# RS232_485.net
KiCad netlist of a schematic drawn in Altium Designer
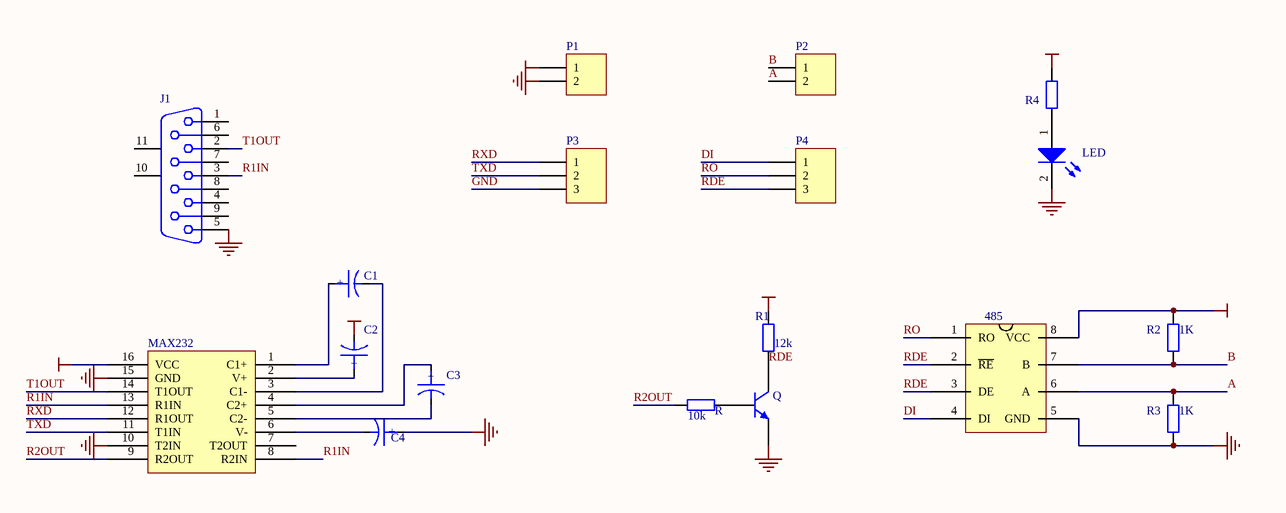
[diagram p0: RS232转485通讯模块.SCHDOC]

(export (version "E")
  (design (tool "Eeschema 10.0.6"))
  (components
    (comp (ref "485") (value "~") (footprint "DIP-8") (libsource (lib "zxcourhc") (part "485芯片")))
    (comp (ref "C1")
      (value "~")
      (footprint "C-DJ-4")
      (description "Capacitor")
      (libsource (lib "") (part "CAPACITOR POL_1"))
    )
    (comp (ref "C2")
      (value "~")
      (footprint "C-DJ-4")
      (description "Capacitor")
      (libsource (lib "") (part "CAPACITOR POL_1"))
    )
    (comp (ref "C3")
      (value "~")
      (footprint "C-DJ-4")
      (description "Capacitor")
      (libsource (lib "") (part "CAPACITOR POL_1"))
    )
    (comp (ref "C4")
      (value "~")
      (footprint "C-DJ-4")
      (description "Capacitor")
      (libsource (lib "*") (part "CAPACITOR POL"))
    )
    (comp (ref "J1")
      (value "~")
      (footprint "DSUB1.385-2H9")
      (description "Receptacle Assembly, 9 Position, Right Angle")
      (fields (field (name "PUBLISHER") "Altium Limited"))
      (libsource (lib "Miscellaneous Connectors") (part "D Connector 9"))
    )
    (comp (ref "LED")
      (value "~")
      (footprint "TP-0805-D")
      (description "发光二极管")
      (fields (field (name "PUBLISHER") "Altium Limited"))
      (libsource (lib "zxcourhc") (part "LED"))
    )
    (comp (ref "MAX232") (value "~") (footprint "DIP16") (libsource (lib "*") (part "MAX232")))
    (comp (ref "P1")
      (value "~")
      (footprint "JK128_2")
      (description "排针——2")
      (fields (field (name "PUBLISHER") "Altium Limited"))
      (libsource (lib "zxcourhc") (part "PZ_2"))
    )
    (comp (ref "P2")
      (value "~")
      (footprint "JK128_2")
      (description "排针——2")
      (fields (field (name "PUBLISHER") "Altium Limited"))
      (libsource (lib "zxcourhc") (part "PZ_2"))
    )
    (comp (ref "P3")
      (value "~")
      (footprint "HDR-3")
      (description "排针——3")
      (fields (field (name "PUBLISHER") "Altium Limited"))
      (libsource (lib "zxcourhc") (part "PZ_3"))
    )
    (comp (ref "P4")
      (value "~")
      (footprint "HDR-3")
      (description "排针——3")
      (fields (field (name "PUBLISHER") "Altium Limited"))
      (libsource (lib "zxcourhc") (part "PZ_3"))
    )
    (comp (ref "Q")
      (value "~")
      (footprint "SO-G3")
      (description "贴片三极管——NPN")
      (fields (field (name "PUBLISHER") "Altium Limited"))
      (libsource (lib "zxcourhc") (part "TPSJG_NPN"))
    )
    (comp (ref "R")
      (value "10k")
      (footprint "TP-0805-R")
      (description "电阻")
      (fields (field (name "PUBLISHER") "Altium Limited"))
      (libsource (lib "") (part "Res_2"))
    )
    (comp (ref "R1")
      (value "12k")
      (footprint "TP-0805-R")
      (description "电阻")
      (fields (field (name "PUBLISHER") "Altium Limited"))
      (libsource (lib "") (part "Res_1"))
    )
    (comp (ref "R2")
      (value "1K")
      (footprint "TP-0805-R")
      (description "电阻")
      (fields (field (name "PUBLISHER") "Altium Limited"))
      (libsource (lib "zxcourhc") (part "Res"))
    )
    (comp (ref "R3")
      (value "1K")
      (footprint "TP-0805-R")
      (description "电阻")
      (fields (field (name "PUBLISHER") "Altium Limited"))
      (libsource (lib "zxcourhc") (part "Res"))
    )
    (comp (ref "R4")
      (value "~")
      (footprint "TP-0805-R")
      (description "电阻")
      (fields (field (name "PUBLISHER") "Altium Limited"))
      (libsource (lib "") (part "Res_1"))
    )
  )
  (nets
    (net (code "1") (name "/A") (class "Default")
      (node (ref "485") (pin "6") (pinfunction "A_6") (pintype "passive"))
      (node (ref "P2") (pin "2") (pinfunction "2_2") (pintype "passive"))
      (node (ref "R3") (pin "1") (pinfunction "1_1") (pintype "passive"))
    )
    (net (code "2") (name "/B") (class "Default")
      (node (ref "485") (pin "7") (pinfunction "B_7") (pintype "passive"))
      (node (ref "P2") (pin "1") (pinfunction "1_1") (pintype "passive"))
      (node (ref "R2") (pin "2") (pinfunction "2_2") (pintype "passive"))
    )
    (net (code "3") (name "/DI") (class "Default")
      (node (ref "485") (pin "4") (pinfunction "DI_4") (pintype "passive"))
      (node (ref "P4") (pin "1") (pinfunction "1_1") (pintype "passive"))
    )
    (net (code "4") (name "/R1IN") (class "Default")
      (node (ref "J1") (pin "3") (pinfunction "3_3") (pintype "passive"))
      (node (ref "MAX232") (pin "13") (pinfunction "R1IN_13") (pintype "passive"))
      (node (ref "MAX232") (pin "8") (pinfunction "R2IN_8") (pintype "passive"))
    )
    (net (code "5") (name "/R2OUT") (class "Default")
      (node (ref "MAX232") (pin "9") (pinfunction "R2OUT_9") (pintype "passive"))
      (node (ref "R") (pin "1") (pinfunction "1_1") (pintype "passive"))
    )
    (net (code "6") (name "/RDE") (class "Default")
      (node (ref "485") (pin "2") (pinfunction "~{RE}_2") (pintype "passive"))
      (node (ref "485") (pin "3") (pinfunction "DE_3") (pintype "passive"))
      (node (ref "P4") (pin "3") (pinfunction "3_3") (pintype "passive"))
      (node (ref "Q") (pin "3") (pinfunction "C_3") (pintype "passive"))
      (node (ref "R1") (pin "1") (pinfunction "1_1") (pintype "passive"))
    )
    (net (code "7") (name "/RO") (class "Default")
      (node (ref "485") (pin "1") (pinfunction "RO_1") (pintype "passive"))
      (node (ref "P4") (pin "2") (pinfunction "2_2") (pintype "passive"))
    )
    (net (code "8") (name "/RXD") (class "Default")
      (node (ref "MAX232") (pin "12") (pinfunction "R1OUT_12") (pintype "passive"))
      (node (ref "P3") (pin "1") (pinfunction "1_1") (pintype "passive"))
    )
    (net (code "9") (name "/T1OUT") (class "Default")
      (node (ref "J1") (pin "2") (pinfunction "2_2") (pintype "passive"))
      (node (ref "MAX232") (pin "14") (pinfunction "T1OUT_14") (pintype "passive"))
    )
    (net (code "10") (name "/TXD") (class "Default")
      (node (ref "MAX232") (pin "11") (pinfunction "T1IN_11") (pintype "passive"))
      (node (ref "P3") (pin "2") (pinfunction "2_2") (pintype "passive"))
    )
    (net (code "11") (name "GND") (class "Default")
      (node (ref "485") (pin "5") (pinfunction "GND_5") (pintype "passive"))
      (node (ref "C4") (pin "1") (pinfunction "1_1") (pintype "passive"))
      (node (ref "J1") (pin "5") (pinfunction "5_5") (pintype "passive"))
      (node (ref "LED") (pin "2") (pinfunction "K_2") (pintype "passive"))
      (node (ref "MAX232") (pin "10") (pinfunction "T2IN_10") (pintype "passive"))
      (node (ref "MAX232") (pin "15") (pinfunction "GND_15") (pintype "passive"))
      (node (ref "P1") (pin "2") (pinfunction "2_2") (pintype "passive"))
      (node (ref "P3") (pin "3") (pinfunction "3_3") (pintype "passive"))
      (node (ref "Q") (pin "2") (pinfunction "E_2") (pintype "passive"))
      (node (ref "R3") (pin "2") (pinfunction "2_2") (pintype "passive"))
    )
    (net (code "12") (name "Net-(LED-A)") (class "Default")
      (node (ref "LED") (pin "1") (pinfunction "A_1") (pintype "passive"))
      (node (ref "R4") (pin "1") (pinfunction "1_1") (pintype "passive"))
    )
    (net (code "13") (name "Net-(MAX232-C1+)") (class "Default")
      (node (ref "C1") (pin "1") (pinfunction "1_1") (pintype "passive"))
      (node (ref "MAX232") (pin "1") (pinfunction "C1+_1") (pintype "passive"))
    )
    (net (code "14") (name "Net-(MAX232-C1-)") (class "Default")
      (node (ref "C1") (pin "2") (pinfunction "2_2") (pintype "passive"))
      (node (ref "MAX232") (pin "3") (pinfunction "C1-_3") (pintype "passive"))
    )
    (net (code "15") (name "Net-(MAX232-C2+)") (class "Default")
      (node (ref "C3") (pin "1") (pinfunction "1_1") (pintype "passive"))
      (node (ref "MAX232") (pin "4") (pinfunction "C2+_4") (pintype "passive"))
    )
    (net (code "16") (name "Net-(MAX232-C2-)") (class "Default")
      (node (ref "C3") (pin "2") (pinfunction "2_2") (pintype "passive"))
      (node (ref "MAX232") (pin "5") (pinfunction "C2-_5") (pintype "passive"))
    )
    (net (code "17") (name "Net-(MAX232-V+)") (class "Default")
      (node (ref "C2") (pin "1") (pinfunction "1_1") (pintype "passive"))
      (node (ref "MAX232") (pin "2") (pinfunction "V+_2") (pintype "passive"))
    )
    (net (code "18") (name "Net-(MAX232-V-)") (class "Default")
      (node (ref "C4") (pin "2") (pinfunction "2_2") (pintype "passive"))
      (node (ref "MAX232") (pin "6") (pinfunction "V-_6") (pintype "passive"))
    )
    (net (code "19") (name "Net-(Q-B)") (class "Default")
      (node (ref "Q") (pin "1") (pinfunction "B_1") (pintype "passive"))
      (node (ref "R") (pin "2") (pinfunction "2_2") (pintype "passive"))
    )
    (net (code "20") (name "VCC") (class "Default")
      (node (ref "485") (pin "8") (pinfunction "VCC_8") (pintype "passive"))
      (node (ref "C2") (pin "2") (pinfunction "2_2") (pintype "passive"))
      (node (ref "MAX232") (pin "16") (pinfunction "VCC_16") (pintype "passive"))
      (node (ref "P1") (pin "1") (pinfunction "1_1") (pintype "passive"))
      (node (ref "R1") (pin "2") (pinfunction "2_2") (pintype "passive"))
      (node (ref "R2") (pin "1") (pinfunction "1_1") (pintype "passive"))
      (node (ref "R4") (pin "2") (pinfunction "2_2") (pintype "passive"))
    )
    (net (code "21") (name "unconnected-(J1-MH1-Pad10)") (class "Default")
      (node (ref "J1") (pin "10") (pinfunction "MH1_10") (pintype "passive"))
    )
    (net (code "22") (name "unconnected-(J1-MH2-Pad11)") (class "Default")
      (node (ref "J1") (pin "11") (pinfunction "MH2_11") (pintype "passive"))
    )
    (net (code "23") (name "unconnected-(J1-Pad1)") (class "Default")
      (node (ref "J1") (pin "1") (pinfunction "1_1") (pintype "passive"))
    )
    (net (code "24") (name "unconnected-(J1-Pad4)") (class "Default")
      (node (ref "J1") (pin "4") (pinfunction "4_4") (pintype "passive"))
    )
    (net (code "25") (name "unconnected-(J1-Pad6)") (class "Default")
      (node (ref "J1") (pin "6") (pinfunction "6_6") (pintype "passive"))
    )
    (net (code "26") (name "unconnected-(J1-Pad7)") (class "Default")
      (node (ref "J1") (pin "7") (pinfunction "7_7") (pintype "passive"))
    )
    (net (code "27") (name "unconnected-(J1-Pad8)") (class "Default")
      (node (ref "J1") (pin "8") (pinfunction "8_8") (pintype "passive"))
    )
    (net (code "28") (name "unconnected-(J1-Pad9)") (class "Default")
      (node (ref "J1") (pin "9") (pinfunction "9_9") (pintype "passive"))
    )
    (net (code "29") (name "unconnected-(MAX232-T2OUT-Pad7)") (class "Default")
      (node (ref "MAX232") (pin "7") (pinfunction "T2OUT_7") (pintype "passive"))
    )
  )
)
